# onion_ws2812.net
KiCad netlist of a schematic drawn in EAGLE
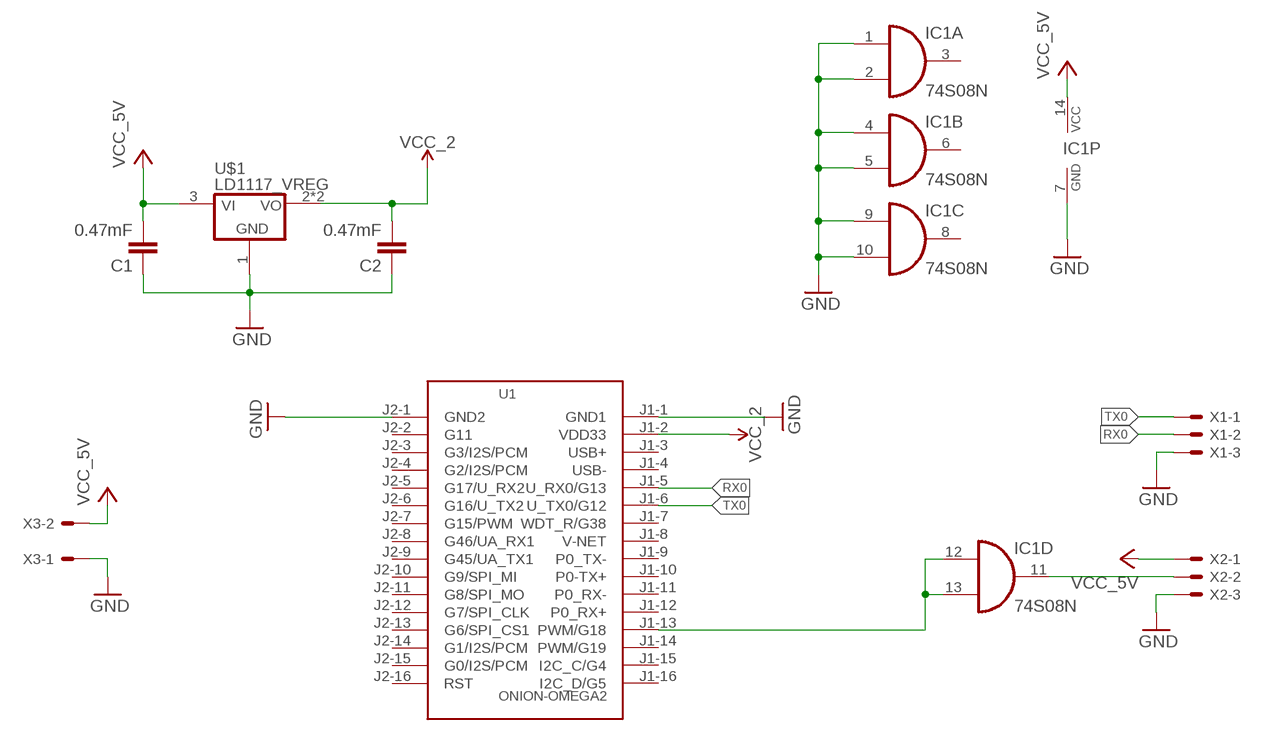
[diagram p0: schematic, sheet 1]

(export (version "E")
  (design (tool "Eeschema 10.0.6"))
  (components
    (comp (ref "C1")
      (value "0.47mF")
      (footprint "eagle-import:C1206")
      (libsource (lib "eagle-import") (part "C-1206"))
    )
    (comp (ref "C2")
      (value "0.47mF")
      (footprint "eagle-import:C1206")
      (libsource (lib "eagle-import") (part "C-1206"))
    )
    (comp (ref "IC1")
      (value "74S08N")
      (footprint "eagle-import:DIL14")
      (libsource (lib "eagle-import") (part "7408NS"))
    )
    (comp (ref "U$1")
      (value "LD1117_VREG")
      (footprint "eagle-import:SOT-223")
      (libsource (lib "eagle-import") (part "LD1117_VREG"))
    )
    (comp (ref "U1")
      (value "ONION-OMEGA2")
      (footprint "eagle-import:ONION-2MM-2X16")
      (libsource (lib "eagle-import") (part "ONION-OMEGA2"))
    )
    (comp (ref "X1")
      (value "KK-156-3")
      (footprint "eagle-import:KK-156-3")
      (libsource (lib "eagle-import") (part "KK-156-3"))
    )
    (comp (ref "X2")
      (value "KK-156-3")
      (footprint "eagle-import:KK-156-3")
      (libsource (lib "eagle-import") (part "KK-156-3"))
    )
    (comp (ref "X3")
      (value "KK-156-2")
      (footprint "eagle-import:KK-156-2")
      (libsource (lib "eagle-import") (part "KK-156-2"))
    )
  )
  (nets
    (net (code "1") (name "GND") (class "Default")
      (node (ref "C1") (pin "1") (pinfunction "1_1") (pintype "passive"))
      (node (ref "C2") (pin "1") (pinfunction "1_1") (pintype "passive"))
      (node (ref "IC1") (pin "1") (pinfunction "I0_1") (pintype "input"))
      (node (ref "IC1") (pin "10") (pinfunction "I1_10") (pintype "input"))
      (node (ref "IC1") (pin "2") (pinfunction "I1_2") (pintype "input"))
      (node (ref "IC1") (pin "4") (pinfunction "I0_4") (pintype "input"))
      (node (ref "IC1") (pin "5") (pinfunction "I1_5") (pintype "input"))
      (node (ref "IC1") (pin "7") (pinfunction "GND_7") (pintype "power_in"))
      (node (ref "IC1") (pin "9") (pinfunction "I0_9") (pintype "input"))
      (node (ref "U$1") (pin "1") (pinfunction "GND_1") (pintype "power_in"))
      (node (ref "U1") (pin "J1-1") (pinfunction "GND1_J1-1") (pintype "bidirectional"))
      (node (ref "U1") (pin "J2-1") (pinfunction "GND2_J2-1") (pintype "bidirectional"))
      (node (ref "X1") (pin "3") (pinfunction "S_3") (pintype "passive"))
      (node (ref "X2") (pin "3") (pinfunction "S_3") (pintype "passive"))
      (node (ref "X3") (pin "1") (pinfunction "S_1") (pintype "passive"))
    )
    (net (code "2") (name "Net-(IC1D-I0)") (class "Default")
      (node (ref "IC1") (pin "12") (pinfunction "I0_12") (pintype "input"))
      (node (ref "IC1") (pin "13") (pinfunction "I1_13") (pintype "input"))
      (node (ref "U1") (pin "J1-13") (pinfunction "PWM/G18_J1-13") (pintype "bidirectional"))
    )
    (net (code "3") (name "Net-(IC1D-O)") (class "Default")
      (node (ref "IC1") (pin "11") (pinfunction "O_11") (pintype "output"))
      (node (ref "X2") (pin "2") (pinfunction "S_2") (pintype "passive"))
    )
    (net (code "4") (name "RX0") (class "Default")
      (node (ref "U1") (pin "J1-5") (pinfunction "U_RX0/G13_J1-5") (pintype "bidirectional"))
      (node (ref "X1") (pin "2") (pinfunction "S_2") (pintype "passive"))
    )
    (net (code "5") (name "TX0") (class "Default")
      (node (ref "U1") (pin "J1-6") (pinfunction "U_TX0/G12_J1-6") (pintype "bidirectional"))
      (node (ref "X1") (pin "1") (pinfunction "S_1") (pintype "passive"))
    )
    (net (code "6") (name "VCC_2") (class "Default")
      (node (ref "C2") (pin "2") (pinfunction "2_2") (pintype "passive"))
      (node (ref "U$1") (pin "2") (pinfunction "VOUT_2") (pintype "passive"))
      (node (ref "U$1") (pin "TAB") (pinfunction "VOUT_TAB") (pintype "passive"))
      (node (ref "U1") (pin "J1-2") (pinfunction "VDD33_J1-2") (pintype "bidirectional"))
    )
    (net (code "7") (name "VCC_5V") (class "Default")
      (node (ref "C1") (pin "2") (pinfunction "2_2") (pintype "passive"))
      (node (ref "IC1") (pin "14") (pinfunction "VCC_14") (pintype "power_in"))
      (node (ref "U$1") (pin "3") (pinfunction "VIN_3") (pintype "power_in"))
      (node (ref "X2") (pin "1") (pinfunction "S_1") (pintype "passive"))
      (node (ref "X3") (pin "2") (pinfunction "S_2") (pintype "passive"))
    )
    (net (code "8") (name "unconnected-(IC1A-O-Pad3)") (class "Default")
      (node (ref "IC1") (pin "3") (pinfunction "O_3") (pintype "output"))
    )
    (net (code "9") (name "unconnected-(IC1B-O-Pad6)") (class "Default")
      (node (ref "IC1") (pin "6") (pinfunction "O_6") (pintype "output"))
    )
    (net (code "10") (name "unconnected-(IC1C-O-Pad8)") (class "Default")
      (node (ref "IC1") (pin "8") (pinfunction "O_8") (pintype "output"))
    )
    (net (code "11") (name "unconnected-(U1-G0{slash}I2S{slash}PCM-PadJ2-15)") (class "Default")
      (node (ref "U1") (pin "J2-15") (pinfunction "G0/I2S/PCM_J2-15") (pintype "bidirectional"))
    )
    (net (code "12") (name "unconnected-(U1-G1{slash}I2S{slash}PCM-PadJ2-14)") (class "Default")
      (node (ref "U1") (pin "J2-14") (pinfunction "G1/I2S/PCM_J2-14") (pintype "bidirectional"))
    )
    (net (code "13") (name "unconnected-(U1-G2{slash}I2S{slash}PCM-PadJ2-4)") (class "Default")
      (node (ref "U1") (pin "J2-4") (pinfunction "G2/I2S/PCM_J2-4") (pintype "bidirectional"))
    )
    (net (code "14") (name "unconnected-(U1-G3{slash}I2S{slash}PCM-PadJ2-3)") (class "Default")
      (node (ref "U1") (pin "J2-3") (pinfunction "G3/I2S/PCM_J2-3") (pintype "bidirectional"))
    )
    (net (code "15") (name "unconnected-(U1-G6{slash}SPI_CS1-PadJ2-13)") (class "Default")
      (node (ref "U1") (pin "J2-13") (pinfunction "G6/SPI_CS1_J2-13") (pintype "bidirectional"))
    )
    (net (code "16") (name "unconnected-(U1-G7{slash}SPI_CLK-PadJ2-12)") (class "Default")
      (node (ref "U1") (pin "J2-12") (pinfunction "G7/SPI_CLK_J2-12") (pintype "bidirectional"))
    )
    (net (code "17") (name "unconnected-(U1-G8{slash}SPI_MO-PadJ2-11)") (class "Default")
      (node (ref "U1") (pin "J2-11") (pinfunction "G8/SPI_MO_J2-11") (pintype "bidirectional"))
    )
    (net (code "18") (name "unconnected-(U1-G9{slash}SPI_MI-PadJ2-10)") (class "Default")
      (node (ref "U1") (pin "J2-10") (pinfunction "G9/SPI_MI_J2-10") (pintype "bidirectional"))
    )
    (net (code "19") (name "unconnected-(U1-G11-PadJ2-2)") (class "Default")
      (node (ref "U1") (pin "J2-2") (pinfunction "G11_J2-2") (pintype "bidirectional"))
    )
    (net (code "20") (name "unconnected-(U1-G15{slash}PWM-PadJ2-7)") (class "Default")
      (node (ref "U1") (pin "J2-7") (pinfunction "G15/PWM_J2-7") (pintype "bidirectional"))
    )
    (net (code "21") (name "unconnected-(U1-G16{slash}U_TX2-PadJ2-6)") (class "Default")
      (node (ref "U1") (pin "J2-6") (pinfunction "G16/U_TX2_J2-6") (pintype "bidirectional"))
    )
    (net (code "22") (name "unconnected-(U1-G17{slash}U_RX2-PadJ2-5)") (class "Default")
      (node (ref "U1") (pin "J2-5") (pinfunction "G17/U_RX2_J2-5") (pintype "bidirectional"))
    )
    (net (code "23") (name "unconnected-(U1-G45{slash}UA_TX1-PadJ2-9)") (class "Default")
      (node (ref "U1") (pin "J2-9") (pinfunction "G45/UA_TX1_J2-9") (pintype "bidirectional"))
    )
    (net (code "24") (name "unconnected-(U1-G46{slash}UA_RX1-PadJ2-8)") (class "Default")
      (node (ref "U1") (pin "J2-8") (pinfunction "G46/UA_RX1_J2-8") (pintype "bidirectional"))
    )
    (net (code "25") (name "unconnected-(U1-I2C_C{slash}G4-PadJ1-15)") (class "Default")
      (node (ref "U1") (pin "J1-15") (pinfunction "I2C_C/G4_J1-15") (pintype "bidirectional"))
    )
    (net (code "26") (name "unconnected-(U1-I2C_D{slash}G5-PadJ1-16)") (class "Default")
      (node (ref "U1") (pin "J1-16") (pinfunction "I2C_D/G5_J1-16") (pintype "bidirectional"))
    )
    (net (code "27") (name "unconnected-(U1-P0-TX+-PadJ1-10)") (class "Default")
      (node (ref "U1") (pin "J1-10") (pinfunction "P0-TX+_J1-10") (pintype "bidirectional"))
    )
    (net (code "28") (name "unconnected-(U1-P0_RX+-PadJ1-12)") (class "Default")
      (node (ref "U1") (pin "J1-12") (pinfunction "P0_RX+_J1-12") (pintype "bidirectional"))
    )
    (net (code "29") (name "unconnected-(U1-P0_RX--PadJ1-11)") (class "Default")
      (node (ref "U1") (pin "J1-11") (pinfunction "P0_RX-_J1-11") (pintype "bidirectional"))
    )
    (net (code "30") (name "unconnected-(U1-P0_TX--PadJ1-9)") (class "Default")
      (node (ref "U1") (pin "J1-9") (pinfunction "P0_TX-_J1-9") (pintype "bidirectional"))
    )
    (net (code "31") (name "unconnected-(U1-PWM{slash}G19-PadJ1-14)") (class "Default")
      (node (ref "U1") (pin "J1-14") (pinfunction "PWM/G19_J1-14") (pintype "bidirectional"))
    )
    (net (code "32") (name "unconnected-(U1-RST-PadJ2-16)") (class "Default")
      (node (ref "U1") (pin "J2-16") (pinfunction "RST_J2-16") (pintype "bidirectional"))
    )
    (net (code "33") (name "unconnected-(U1-USB+-PadJ1-3)") (class "Default")
      (node (ref "U1") (pin "J1-3") (pinfunction "USB+_J1-3") (pintype "bidirectional"))
    )
    (net (code "34") (name "unconnected-(U1-USB--PadJ1-4)") (class "Default")
      (node (ref "U1") (pin "J1-4") (pinfunction "USB-_J1-4") (pintype "bidirectional"))
    )
    (net (code "35") (name "unconnected-(U1-V-NET-PadJ1-8)") (class "Default")
      (node (ref "U1") (pin "J1-8") (pinfunction "V-NET_J1-8") (pintype "bidirectional"))
    )
    (net (code "36") (name "unconnected-(U1-WDT_R{slash}G38-PadJ1-7)") (class "Default")
      (node (ref "U1") (pin "J1-7") (pinfunction "WDT_R/G38_J1-7") (pintype "bidirectional"))
    )
  )
)
